# InkTime_Schematic.net
KiCad netlist of a schematic drawn in EAGLE
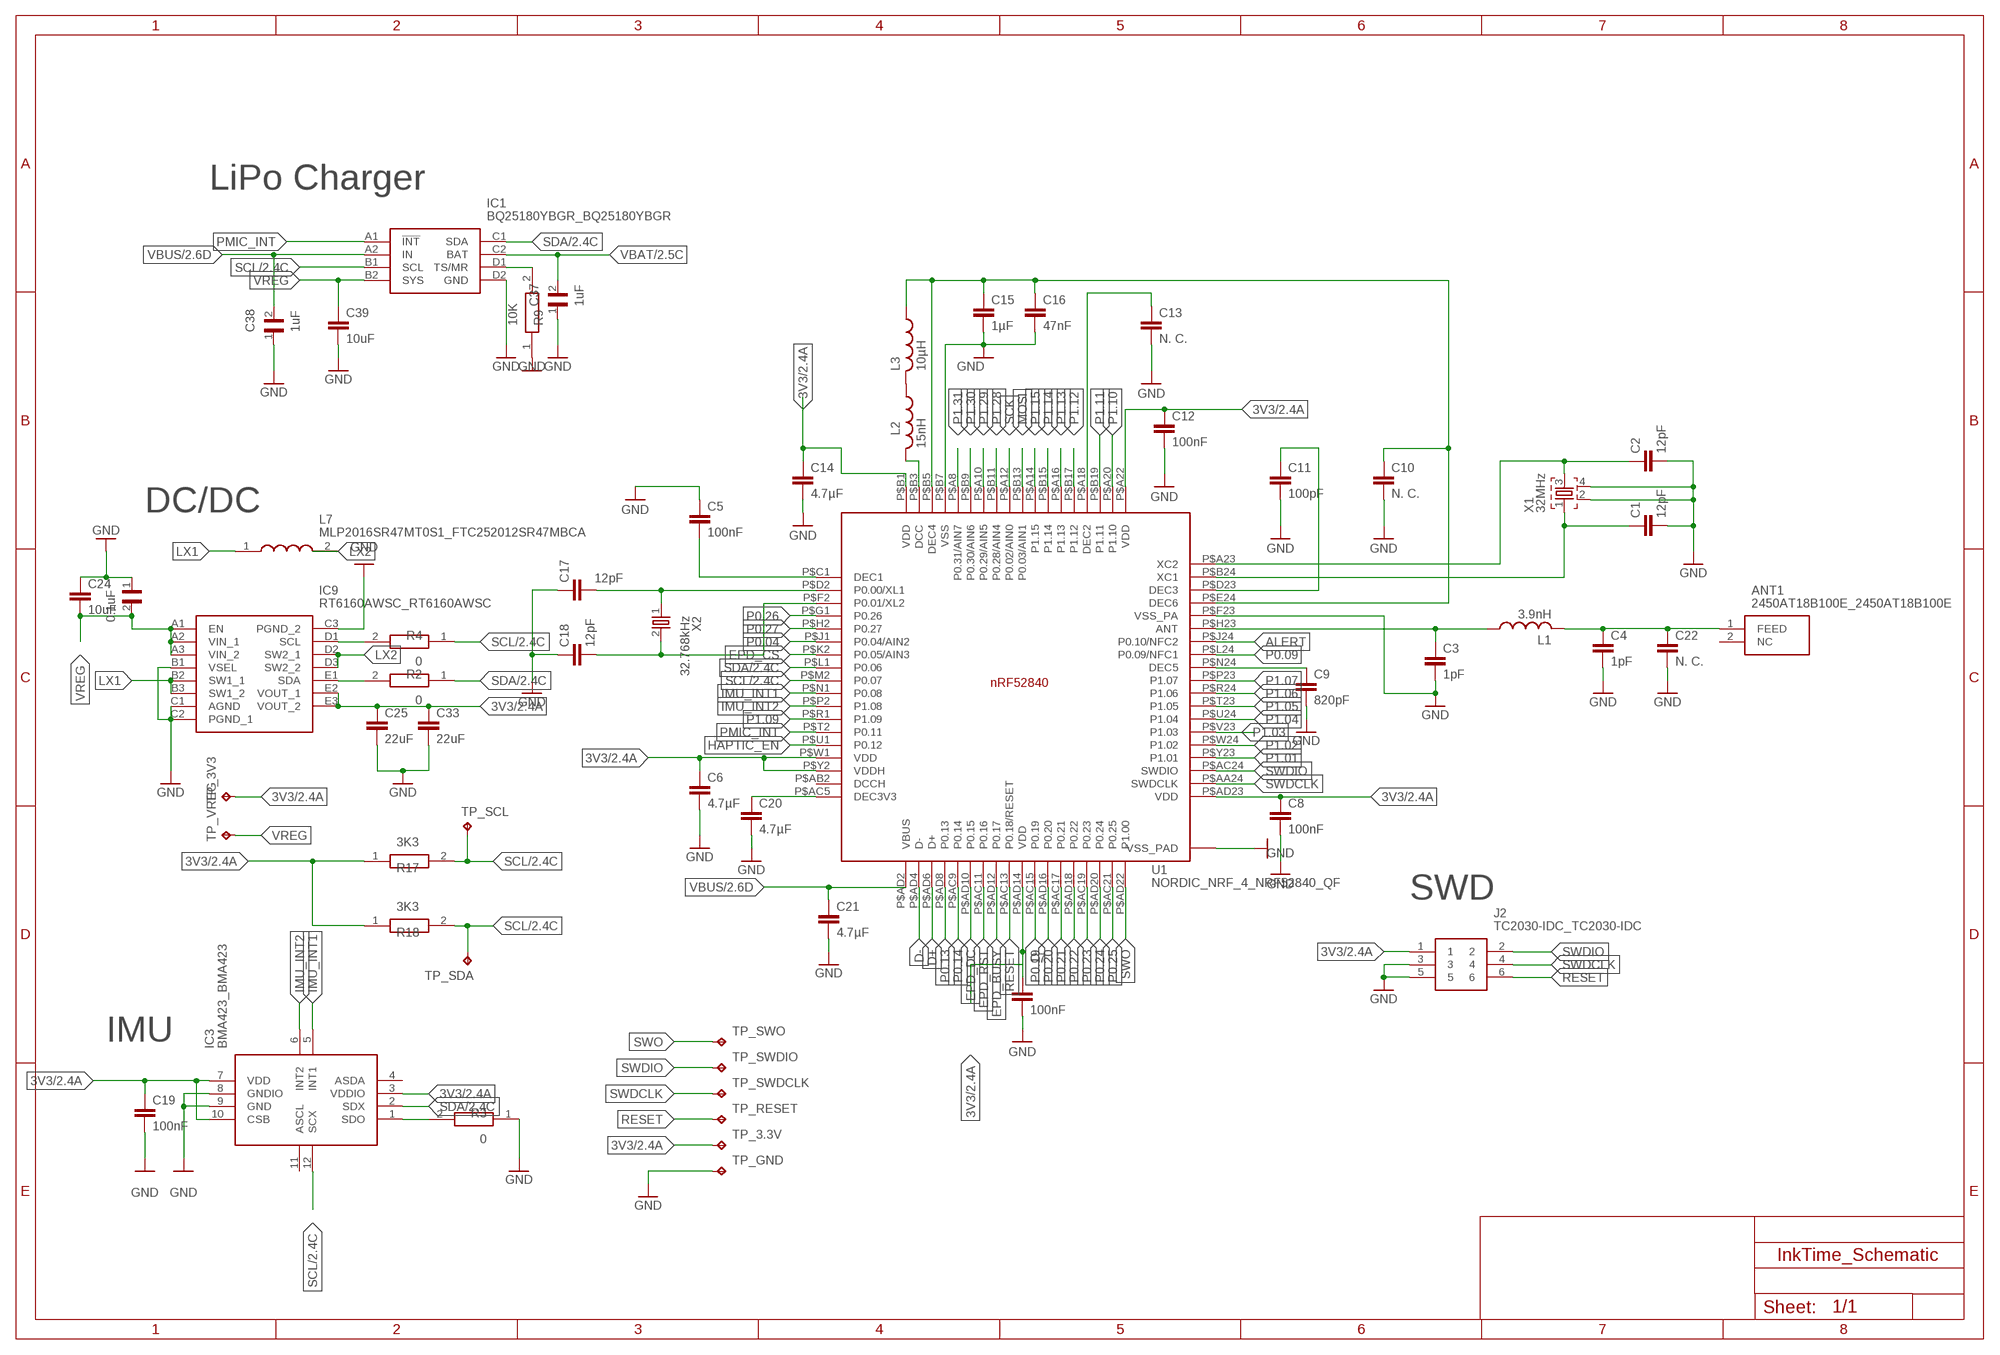
[diagram p0: schematic, sheet 1, part 1 of 2]
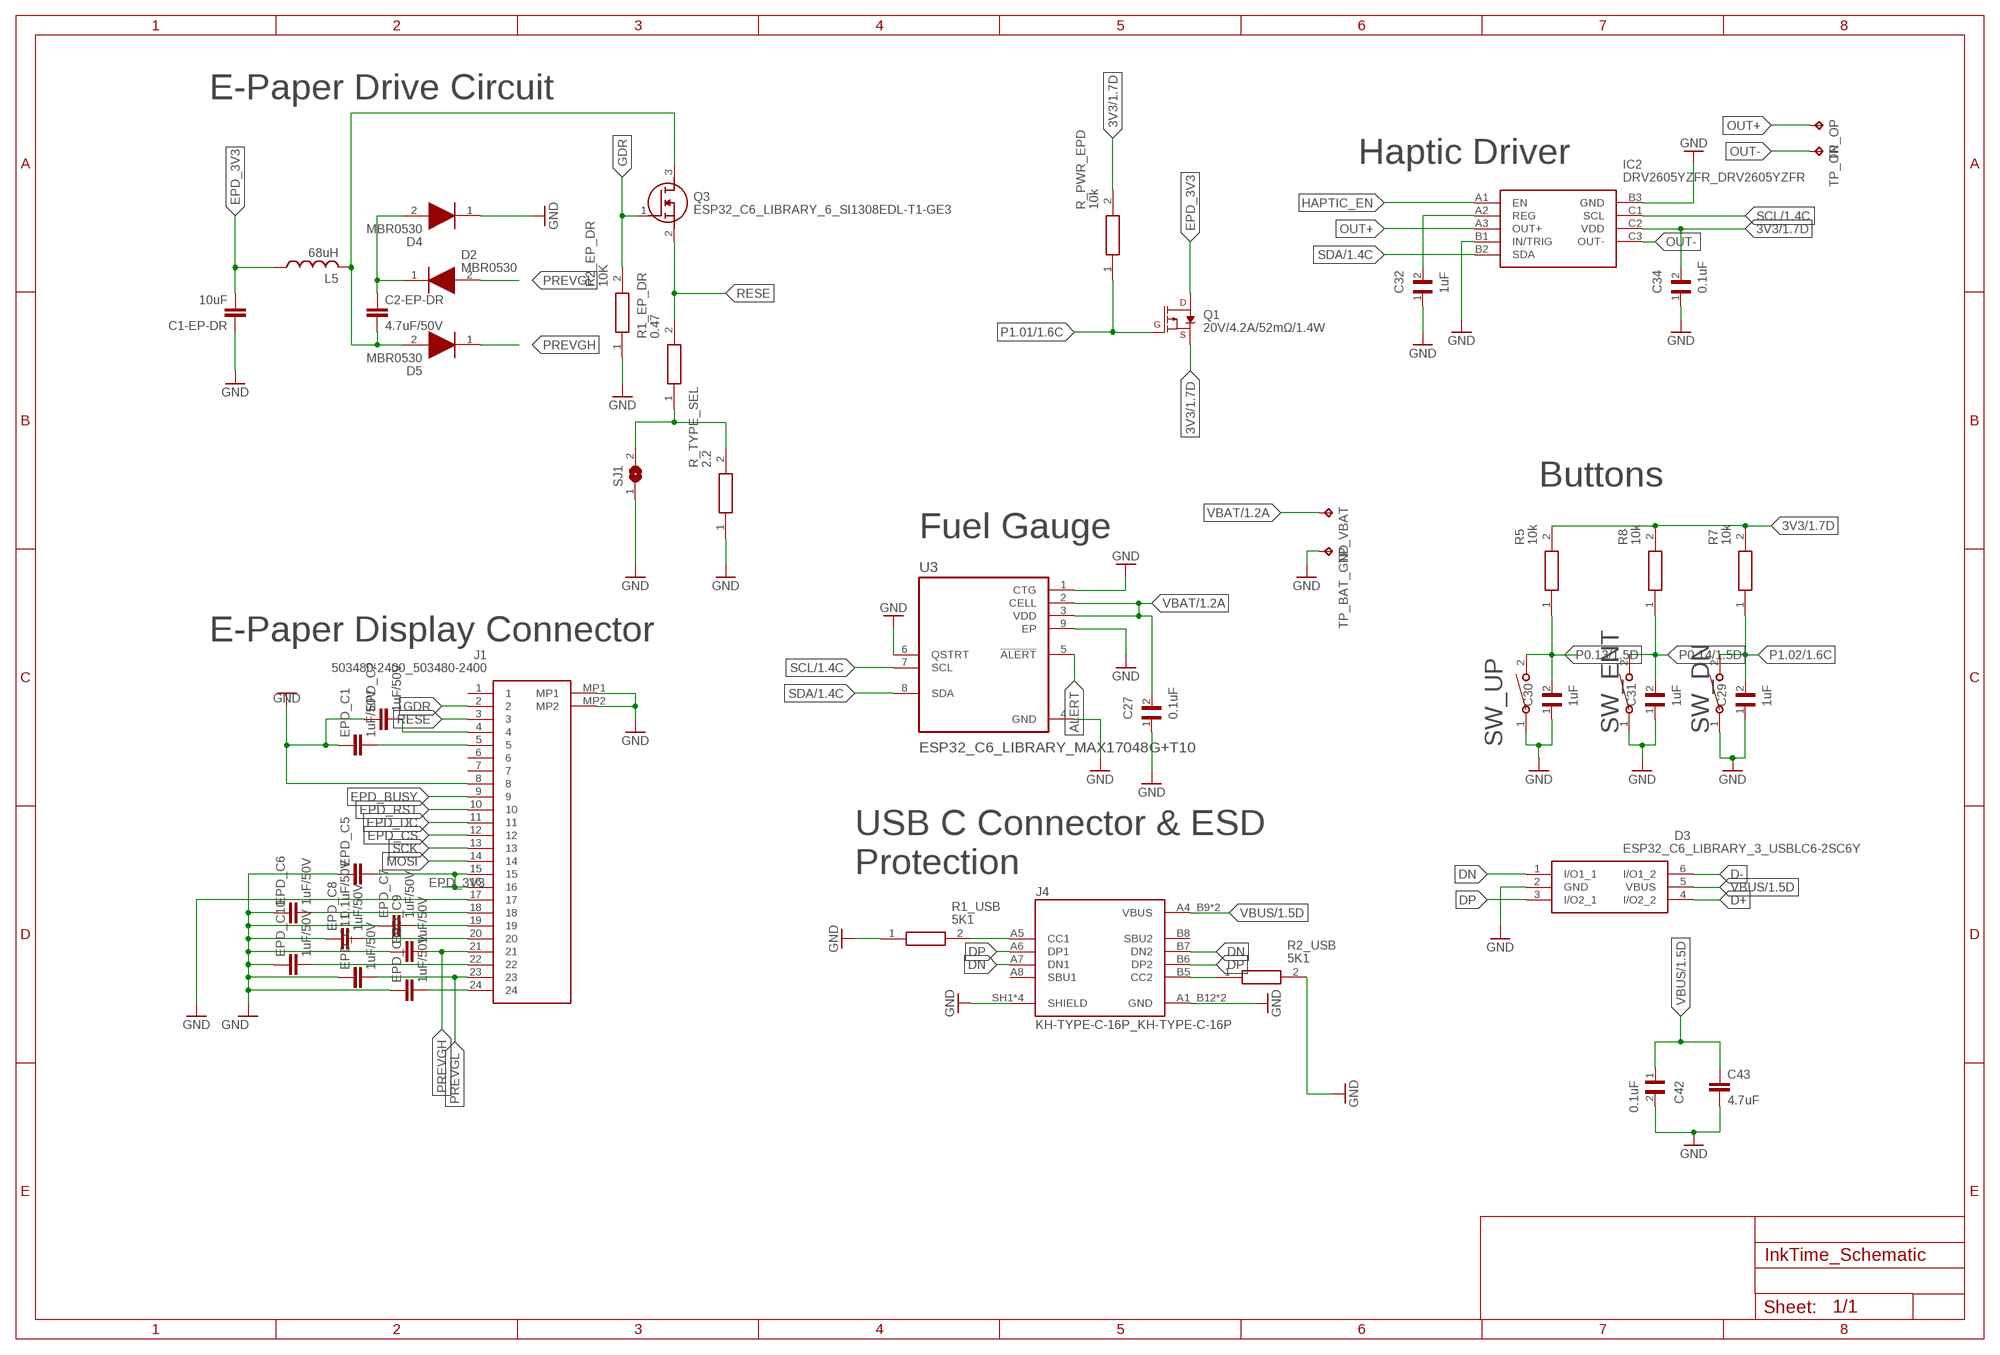
[diagram p1: schematic, sheet 1, part 2 of 2]

(export (version "E")
  (design (tool "Eeschema 10.0.6"))
  (components
    (comp (ref "ANT1")
      (value "2450AT18B100E_2450AT18B100E")
      (footprint "eagle-import:2450AT18B100E_ANTC3216X140N")
      (fields
        (field (name "ARROW_PART_NUMBER") "2450AT18B100E")
        (field (name "MOUSER_PART_NUMBER") "609-2450AT18B100E")
      )
      (libsource (lib "eagle-import") (part "2450AT18B100E_2450AT18B100E"))
    )
    (comp (ref "C1")
      (value "12pF")
      (footprint "eagle-import:NORDIC_NRF_3_RESC0201_L")
      (libsource (lib "eagle-import") (part "NORDIC_NRF_3_CAPACITOR_0201_L"))
    )
    (comp (ref "C1-EP-DR")
      (value "10uF")
      (footprint "eagle-import:NORDIC_NRF_3_RESC0402_L")
      (libsource (lib "eagle-import") (part "NORDIC_NRF_3_CAPACITOR_0402_L"))
    )
    (comp (ref "C2")
      (value "12pF")
      (footprint "eagle-import:NORDIC_NRF_3_RESC0201_L")
      (libsource (lib "eagle-import") (part "NORDIC_NRF_3_CAPACITOR_0201_L"))
    )
    (comp (ref "C2-EP-DR")
      (value "4.7uF/50V")
      (footprint "eagle-import:NORDIC_NRF_3_RESC0402_L")
      (libsource (lib "eagle-import") (part "NORDIC_NRF_3_CAPACITOR_0402_L"))
    )
    (comp (ref "C3")
      (value "1pF")
      (footprint "eagle-import:NORDIC_NRF_3_RESC0201_L")
      (libsource (lib "eagle-import") (part "NORDIC_NRF_3_CAPACITOR_0201_L"))
    )
    (comp (ref "C4")
      (value "1pF")
      (footprint "eagle-import:NORDIC_NRF_3_RESC0201_L")
      (libsource (lib "eagle-import") (part "NORDIC_NRF_3_CAPACITOR_0201_L"))
    )
    (comp (ref "C5")
      (value "100nF")
      (footprint "eagle-import:NORDIC_NRF_3_RESC0201_L")
      (libsource (lib "eagle-import") (part "NORDIC_NRF_3_CAPACITOR_0201_L"))
    )
    (comp (ref "C6")
      (value "4.7µF")
      (footprint "eagle-import:NORDIC_NRF_3_RESC0402_L")
      (libsource (lib "eagle-import") (part "NORDIC_NRF_3_CAPACITOR_0402_L"))
    )
    (comp (ref "C7")
      (value "100nF")
      (footprint "eagle-import:NORDIC_NRF_3_RESC0201_L")
      (libsource (lib "eagle-import") (part "NORDIC_NRF_3_CAPACITOR_0201_L"))
    )
    (comp (ref "C8")
      (value "100nF")
      (footprint "eagle-import:NORDIC_NRF_3_RESC0201_L")
      (libsource (lib "eagle-import") (part "NORDIC_NRF_3_CAPACITOR_0201_L"))
    )
    (comp (ref "C9")
      (value "820pF")
      (footprint "eagle-import:NORDIC_NRF_3_RESC0201_L")
      (libsource (lib "eagle-import") (part "NORDIC_NRF_3_CAPACITOR_0201_L"))
    )
    (comp (ref "C10")
      (value "N. C.")
      (footprint "eagle-import:NORDIC_NRF_3_RESC0201_L")
      (libsource (lib "eagle-import") (part "NORDIC_NRF_3_CAPACITOR_0201_L"))
    )
    (comp (ref "C11")
      (value "100pF")
      (footprint "eagle-import:NORDIC_NRF_3_RESC0201_L")
      (libsource (lib "eagle-import") (part "NORDIC_NRF_3_CAPACITOR_0201_L"))
    )
    (comp (ref "C12")
      (value "100nF")
      (footprint "eagle-import:NORDIC_NRF_3_RESC0201_L")
      (libsource (lib "eagle-import") (part "NORDIC_NRF_3_CAPACITOR_0201_L"))
    )
    (comp (ref "C13")
      (value "N. C.")
      (footprint "eagle-import:NORDIC_NRF_3_RESC0201_L")
      (libsource (lib "eagle-import") (part "NORDIC_NRF_3_CAPACITOR_0201_L"))
    )
    (comp (ref "C14")
      (value "4.7µF")
      (footprint "eagle-import:NORDIC_NRF_3_RESC0402_L")
      (libsource (lib "eagle-import") (part "NORDIC_NRF_3_CAPACITOR_0402_L"))
    )
    (comp (ref "C15")
      (value "1µF")
      (footprint "eagle-import:NORDIC_NRF_3_RESC0402_L")
      (libsource (lib "eagle-import") (part "NORDIC_NRF_3_CAPACITOR_0402_L"))
    )
    (comp (ref "C16")
      (value "47nF")
      (footprint "eagle-import:NORDIC_NRF_3_RESC0201_L")
      (libsource (lib "eagle-import") (part "NORDIC_NRF_3_CAPACITOR_0201_L"))
    )
    (comp (ref "C17")
      (value "12pF")
      (footprint "eagle-import:NORDIC_NRF_3_RESC0201_L")
      (libsource (lib "eagle-import") (part "NORDIC_NRF_3_CAPACITOR_0201_L"))
    )
    (comp (ref "C18")
      (value "12pF")
      (footprint "eagle-import:NORDIC_NRF_3_RESC0201_L")
      (libsource (lib "eagle-import") (part "NORDIC_NRF_3_CAPACITOR_0201_L"))
    )
    (comp (ref "C19")
      (value "100nF")
      (footprint "eagle-import:NORDIC_NRF_3_RESC0201_L")
      (libsource (lib "eagle-import") (part "NORDIC_NRF_3_CAPACITOR_0201_L"))
    )
    (comp (ref "C20")
      (value "4.7µF")
      (footprint "eagle-import:NORDIC_NRF_3_RESC0402_L")
      (libsource (lib "eagle-import") (part "NORDIC_NRF_3_CAPACITOR_0402_L"))
    )
    (comp (ref "C21")
      (value "4.7µF")
      (footprint "eagle-import:NORDIC_NRF_3_RESC0402_L")
      (libsource (lib "eagle-import") (part "NORDIC_NRF_3_CAPACITOR_0402_L"))
    )
    (comp (ref "C22")
      (value "N. C.")
      (footprint "eagle-import:NORDIC_NRF_3_RESC0201_L")
      (libsource (lib "eagle-import") (part "NORDIC_NRF_3_CAPACITOR_0201_L"))
    )
    (comp (ref "C23")
      (value "0.1uF")
      (footprint "eagle-import:GRM011R60J152KE01L_1_0201")
      (libsource (lib "eagle-import") (part "GRM011R60J152KE01L_1_GRM011R60J152KE01L"))
    )
    (comp (ref "C24")
      (value "10uF")
      (footprint "eagle-import:NORDIC_NRF_3_RESC0402_L")
      (libsource (lib "eagle-import") (part "NORDIC_NRF_3_CAPACITOR_0402_L"))
    )
    (comp (ref "C25")
      (value "22uF")
      (footprint "eagle-import:NORDIC_NRF_3_RESC0402_L")
      (libsource (lib "eagle-import") (part "NORDIC_NRF_3_CAPACITOR_0402_L"))
    )
    (comp (ref "C27")
      (value "0.1uF")
      (footprint "eagle-import:GRM011R60J152KE01L_1_0201")
      (libsource (lib "eagle-import") (part "GRM011R60J152KE01L_1_GRM011R60J152KE01L"))
    )
    (comp (ref "C29")
      (value "1uF")
      (footprint "eagle-import:GRM011R60J152KE01L_1_0201")
      (libsource (lib "eagle-import") (part "GRM011R60J152KE01L_1_GRM011R60J152KE01L"))
    )
    (comp (ref "C30")
      (value "1uF")
      (footprint "eagle-import:GRM011R60J152KE01L_1_0201")
      (libsource (lib "eagle-import") (part "GRM011R60J152KE01L_1_GRM011R60J152KE01L"))
    )
    (comp (ref "C31")
      (value "1uF")
      (footprint "eagle-import:GRM011R60J152KE01L_1_0201")
      (libsource (lib "eagle-import") (part "GRM011R60J152KE01L_1_GRM011R60J152KE01L"))
    )
    (comp (ref "C32")
      (value "1uF")
      (footprint "eagle-import:GRM011R60J152KE01L_1_0201")
      (libsource (lib "eagle-import") (part "GRM011R60J152KE01L_1_GRM011R60J152KE01L"))
    )
    (comp (ref "C33")
      (value "22uF")
      (footprint "eagle-import:NORDIC_NRF_3_RESC0402_L")
      (libsource (lib "eagle-import") (part "NORDIC_NRF_3_CAPACITOR_0402_L"))
    )
    (comp (ref "C34")
      (value "0.1uF")
      (footprint "eagle-import:GRM011R60J152KE01L_1_0201")
      (libsource (lib "eagle-import") (part "GRM011R60J152KE01L_1_GRM011R60J152KE01L"))
    )
    (comp (ref "C37")
      (value "1uF")
      (footprint "eagle-import:GRM011R60J152KE01L_1_0201")
      (libsource (lib "eagle-import") (part "GRM011R60J152KE01L_1_GRM011R60J152KE01L"))
    )
    (comp (ref "C38")
      (value "1uF")
      (footprint "eagle-import:GRM011R60J152KE01L_1_0201")
      (libsource (lib "eagle-import") (part "GRM011R60J152KE01L_1_GRM011R60J152KE01L"))
    )
    (comp (ref "C39")
      (value "10uF")
      (footprint "eagle-import:NORDIC_NRF_3_RESC0402_L")
      (libsource (lib "eagle-import") (part "NORDIC_NRF_3_CAPACITOR_0402_L"))
    )
    (comp (ref "C42")
      (value "0.1uF")
      (footprint "eagle-import:GRM011R60J152KE01L_1_0201")
      (libsource (lib "eagle-import") (part "GRM011R60J152KE01L_1_GRM011R60J152KE01L"))
    )
    (comp (ref "C43")
      (value "4.7uF")
      (footprint "eagle-import:NORDIC_NRF_3_RESC0402_L")
      (libsource (lib "eagle-import") (part "NORDIC_NRF_3_CAPACITOR_0402_L"))
    )
    (comp (ref "D2")
      (value "MBR0530")
      (footprint "eagle-import:ESP32_C6_LIBRARY_5_SOD3716X135N")
      (fields (field (name "MF") "ON Semiconductor"))
      (libsource (lib "eagle-import") (part "ESP32_C6_LIBRARY_5_MBR0530"))
    )
    (comp (ref "D3")
      (value "ESP32_C6_LIBRARY_3_USBLC6-2SC6Y")
      (footprint "eagle-import:ESP32_C6_LIBRARY_3_SOT95P280X145-6N")
      (fields (field (name "MF") "STMicroelectronics") (field (name "MP") "USBLC6-2SC6Y"))
      (libsource (lib "eagle-import") (part "ESP32_C6_LIBRARY_3_USBLC6-2SC6Y"))
    )
    (comp (ref "D4")
      (value "MBR0530")
      (footprint "eagle-import:ESP32_C6_LIBRARY_5_SOD3716X135N")
      (fields (field (name "MF") "ON Semiconductor"))
      (libsource (lib "eagle-import") (part "ESP32_C6_LIBRARY_5_MBR0530"))
    )
    (comp (ref "D5")
      (value "MBR0530")
      (footprint "eagle-import:ESP32_C6_LIBRARY_5_SOD3716X135N")
      (fields (field (name "MF") "ON Semiconductor"))
      (libsource (lib "eagle-import") (part "ESP32_C6_LIBRARY_5_MBR0530"))
    )
    (comp (ref "EPD_C1")
      (value "1uF/50V")
      (footprint "eagle-import:NORDIC_NRF_3_RESC0402_L")
      (libsource (lib "eagle-import") (part "NORDIC_NRF_3_CAPACITOR_0402_L"))
    )
    (comp (ref "EPD_C2")
      (value "1uF/50V")
      (footprint "eagle-import:NORDIC_NRF_3_RESC0402_L")
      (libsource (lib "eagle-import") (part "NORDIC_NRF_3_CAPACITOR_0402_L"))
    )
    (comp (ref "EPD_C5")
      (value "0.1uF/50V")
      (footprint "eagle-import:NORDIC_NRF_3_RESC0201_L")
      (libsource (lib "eagle-import") (part "NORDIC_NRF_3_CAPACITOR_0201_L"))
    )
    (comp (ref "EPD_C6")
      (value "1uF/50V")
      (footprint "eagle-import:NORDIC_NRF_3_RESC0402_L")
      (libsource (lib "eagle-import") (part "NORDIC_NRF_3_CAPACITOR_0402_L"))
    )
    (comp (ref "EPD_C7")
      (value "1uF/50V")
      (footprint "eagle-import:NORDIC_NRF_3_RESC0402_L")
      (libsource (lib "eagle-import") (part "NORDIC_NRF_3_CAPACITOR_0402_L"))
    )
    (comp (ref "EPD_C8")
      (value "1uF/50V")
      (footprint "eagle-import:NORDIC_NRF_3_RESC0402_L")
      (libsource (lib "eagle-import") (part "NORDIC_NRF_3_CAPACITOR_0402_L"))
    )
    (comp (ref "EPD_C9")
      (value "1uF/50V")
      (footprint "eagle-import:NORDIC_NRF_3_RESC0402_L")
      (libsource (lib "eagle-import") (part "NORDIC_NRF_3_CAPACITOR_0402_L"))
    )
    (comp (ref "EPD_C10")
      (value "1uF/50V")
      (footprint "eagle-import:NORDIC_NRF_3_RESC0402_L")
      (libsource (lib "eagle-import") (part "NORDIC_NRF_3_CAPACITOR_0402_L"))
    )
    (comp (ref "EPD_C11")
      (value "1uF/50V")
      (footprint "eagle-import:NORDIC_NRF_3_RESC0402_L")
      (libsource (lib "eagle-import") (part "NORDIC_NRF_3_CAPACITOR_0402_L"))
    )
    (comp (ref "EPD_C12")
      (value "1uF/50V")
      (footprint "eagle-import:NORDIC_NRF_3_RESC0402_L")
      (libsource (lib "eagle-import") (part "NORDIC_NRF_3_CAPACITOR_0402_L"))
    )
    (comp (ref "IC1")
      (value "BQ25180YBGR_BQ25180YBGR")
      (footprint "eagle-import:BQ25180YBGR_BGA8C40P2X4_100X155X50")
      (fields
        (field (name "ARROW_PART_NUMBER") "BQ25180YBGR")
        (field (name "MOUSER_PART_NUMBER") "595-BQ25180YBGR")
      )
      (libsource (lib "eagle-import") (part "BQ25180YBGR_BQ25180YBGR"))
    )
    (comp (ref "IC2")
      (value "DRV2605YZFR_DRV2605YZFR")
      (footprint "eagle-import:DRV2605YZFR_BGA9C50P3X3_144X144X62")
      (fields (field (name "ARROW_PART_NUMBER") "DRV2605YZFR"))
      (libsource (lib "eagle-import") (part "DRV2605YZFR_DRV2605YZFR"))
    )
    (comp (ref "IC3")
      (value "BMA423_BMA423")
      (footprint "eagle-import:BMA423_BMA423")
      (fields (field (name "ARROW_PART_NUMBER") "BMA423") (field (name "MOUSER_PART_NUMBER") "262-BMA423"))
      (libsource (lib "eagle-import") (part "BMA423_BMA423"))
    )
    (comp (ref "IC9")
      (value "RT6160AWSC_RT6160AWSC")
      (footprint "eagle-import:RT6160AWSC_BGA15C40P3X5_140X230X60")
      (fields
        (field (name "MANUFACTURER_PART_NUMBER") "RT6160AWSC")
        (field (name "MOUSER_PART_NUMBER") "835-RT6160AWSC")
      )
      (libsource (lib "eagle-import") (part "RT6160AWSC_RT6160AWSC"))
    )
    (comp (ref "J1")
      (value "503480-2400_503480-2400")
      (footprint "eagle-import:503480-2400_5034802400")
      (fields
        (field (name "MANUFACTURER_PART_NUMBER") "503480-2400")
        (field (name "MOUSER_PART_NUMBER") "538-503480-2400")
      )
      (libsource (lib "eagle-import") (part "503480-2400_503480-2400"))
    )
    (comp (ref "J2")
      (value "TC2030-IDC_TC2030-IDC")
      (footprint "eagle-import:TC2030-IDC_TC2030IDC")
      (fields (field (name "MANUFACTURER_PART_NUMBER") "TC2030-IDC"))
      (libsource (lib "eagle-import") (part "TC2030-IDC_TC2030-IDC"))
    )
    (comp (ref "J4")
      (value "KH-TYPE-C-16P_KH-TYPE-C-16P")
      (footprint "eagle-import:KH-TYPE-C-16P_KINGHELM_KH-TYPE-C-16P")
      (fields (field (name "MF") "kinghelm") (field (name "MP") "KH-TYPE-C-16P"))
      (libsource (lib "eagle-import") (part "KH-TYPE-C-16P_KH-TYPE-C-16P"))
    )
    (comp (ref "L1")
      (value "3.9nH")
      (footprint "eagle-import:NORDIC_NRF_2_RESC0201_L")
      (libsource (lib "eagle-import") (part "NORDIC_NRF_2_INDUCTOR_0201_L"))
    )
    (comp (ref "L2")
      (value "15nH")
      (footprint "eagle-import:NORDIC_NRF_2_RESC0201_L")
      (libsource (lib "eagle-import") (part "NORDIC_NRF_2_INDUCTOR_0201_L"))
    )
    (comp (ref "L3")
      (value "10µH")
      (footprint "eagle-import:NORDIC_NRF_2_RESC0603_L")
      (libsource (lib "eagle-import") (part "NORDIC_NRF_2_INDUCTOR_0603_L"))
    )
    (comp (ref "L5")
      (value "68uH")
      (footprint "eagle-import:NORDIC_NRF_2_RESC0805_L")
      (libsource (lib "eagle-import") (part "NORDIC_NRF_2_INDUCTOR_0805_L"))
    )
    (comp (ref "L7")
      (value "MLP2016SR47MT0S1_FTC252012SR47MBCA")
      (footprint "eagle-import:MLP2016SR47MT0S1_INDC2016X100N")
      (fields (field (name "MANUFACTURER_PART_NUMBER") "FTC252012SR47MBCA"))
      (libsource (lib "eagle-import") (part "MLP2016SR47MT0S1_FTC252012SR47MBCA"))
    )
    (comp (ref "Q1")
      (value "20V/4.2A/52mΩ/1.4W")
      (footprint "eagle-import:ESP32_C6_LIBRARY_4_ESP32_C6_LIBRARY_4_ESP32_C6_LIBRARY_4_ESP32_C6_LIBRARY_4_ESP32_WROVER_SPARKFUN-DISCRETESEMI_SOT23-3")
      (libsource (lib "eagle-import") (part "ESP32_C6_LIBRARY_4_ESP32_WROVER_SPARKFUN-DISCRETESEMI_MOSFET_PCH-DMG2305UX-7"))
    )
    (comp (ref "Q3")
      (value "ESP32_C6_LIBRARY_6_SI1308EDL-T1-GE3")
      (footprint "eagle-import:ESP32_C6_LIBRARY_6_SOT65P210X110-3N")
      (fields (field (name "MF") "Vishay Siliconix") (field (name "MP") "SI1308EDL-T1-GE3"))
      (libsource (lib "eagle-import") (part "ESP32_C6_LIBRARY_6_SI1308EDL-T1-GE3"))
    )
    (comp (ref "R1_EP_DR")
      (value "0.47")
      (footprint "eagle-import:ERA-1AEB3401C_0201")
      (libsource (lib "eagle-import") (part "ERA-1AEB3401C_CPF0201D7K68C1"))
    )
    (comp (ref "R1_USB")
      (value "5K1")
      (footprint "eagle-import:ERA-1AEB3401C_0201")
      (libsource (lib "eagle-import") (part "ERA-1AEB3401C_CPF0201D7K68C1"))
    )
    (comp (ref "R2")
      (value "0")
      (footprint "eagle-import:CPF0201D7K68C1_0201")
      (libsource (lib "eagle-import") (part "CPF0201D7K68C1_CPF0201D7K68C1"))
    )
    (comp (ref "R2_EP_DR")
      (value "10K")
      (footprint "eagle-import:ERA-1AEB3401C_0201")
      (libsource (lib "eagle-import") (part "ERA-1AEB3401C_CPF0201D7K68C1"))
    )
    (comp (ref "R2_USB")
      (value "5K1")
      (footprint "eagle-import:ERA-1AEB3401C_0201")
      (libsource (lib "eagle-import") (part "ERA-1AEB3401C_CPF0201D7K68C1"))
    )
    (comp (ref "R3")
      (value "0")
      (footprint "eagle-import:CPF0201D7K68C1_0201")
      (libsource (lib "eagle-import") (part "CPF0201D7K68C1_CPF0201D7K68C1"))
    )
    (comp (ref "R4")
      (value "0")
      (footprint "eagle-import:CPF0201D7K68C1_0201")
      (libsource (lib "eagle-import") (part "CPF0201D7K68C1_CPF0201D7K68C1"))
    )
    (comp (ref "R5")
      (value "10k")
      (footprint "eagle-import:ERA-1AEB3401C_0201")
      (libsource (lib "eagle-import") (part "ERA-1AEB3401C_CPF0201D7K68C1"))
    )
    (comp (ref "R7")
      (value "10k")
      (footprint "eagle-import:ERA-1AEB3401C_0201")
      (libsource (lib "eagle-import") (part "ERA-1AEB3401C_CPF0201D7K68C1"))
    )
    (comp (ref "R8")
      (value "10k")
      (footprint "eagle-import:ERA-1AEB3401C_0201")
      (libsource (lib "eagle-import") (part "ERA-1AEB3401C_CPF0201D7K68C1"))
    )
    (comp (ref "R9")
      (value "10K")
      (footprint "eagle-import:CPF0201D7K68C1_0201")
      (libsource (lib "eagle-import") (part "CPF0201D7K68C1_CPF0201D7K68C1"))
    )
    (comp (ref "R17")
      (value "3K3")
      (footprint "eagle-import:CPF0201D7K68C1_0201")
      (libsource (lib "eagle-import") (part "CPF0201D7K68C1_CPF0201D7K68C1"))
    )
    (comp (ref "R18")
      (value "3K3")
      (footprint "eagle-import:CPF0201D7K68C1_0201")
      (libsource (lib "eagle-import") (part "CPF0201D7K68C1_CPF0201D7K68C1"))
    )
    (comp (ref "R_PWR_EPD")
      (value "10k")
      (footprint "eagle-import:ERA-1AEB3401C_0201")
      (libsource (lib "eagle-import") (part "ERA-1AEB3401C_CPF0201D7K68C1"))
    )
    (comp (ref "R_TYPE_SEL")
      (value "2.2")
      (footprint "eagle-import:ERA-1AEB3401C_0201")
      (libsource (lib "eagle-import") (part "ERA-1AEB3401C_CPF0201D7K68C1"))
    )
    (comp (ref "SJ1")
      (value "ESP32_C6_LIBRARY_7_JUMPER_SJ")
      (footprint "eagle-import:ESP32_C6_LIBRARY_7_JUMPER_SJ")
      (libsource (lib "eagle-import") (part "ESP32_C6_LIBRARY_7_JUMPER_SJ"))
    )
    (comp (ref "SW_DN")
      (value "2025-10-22_07-23-44_LIBRARY_EVP-AKE31ASW_EVP-AKE31A_PAN")
      (footprint "eagle-import:2025-10-22_07-23-44_LIBRARY_SW_EVP-AKE31A_PAN")
      (fields
        (field (name "MANUFACTURER_PART_NUMBER") "EVP-AKE31A")
        (field (name "COPYRIGHT") "Copyright (C) 2025 Ultra Librarian. All rights reserved.")
      )
      (libsource (lib "eagle-import") (part "2025-10-22_07-23-44_LIBRARY_EVP-AKE31ASW_EVP-AKE31A_PAN"))
    )
    (comp (ref "SW_ENT")
      (value "2025-10-22_07-23-44_LIBRARY_EVP-AKE31ASW_EVP-AKE31A_PAN")
      (footprint "eagle-import:2025-10-22_07-23-44_LIBRARY_SW_EVP-AKE31A_PAN")
      (fields
        (field (name "MANUFACTURER_PART_NUMBER") "EVP-AKE31A")
        (field (name "COPYRIGHT") "Copyright (C) 2025 Ultra Librarian. All rights reserved.")
      )
      (libsource (lib "eagle-import") (part "2025-10-22_07-23-44_LIBRARY_EVP-AKE31ASW_EVP-AKE31A_PAN"))
    )
    (comp (ref "SW_UP")
      (value "2025-10-22_07-23-44_LIBRARY_EVP-AKE31ASW_EVP-AKE31A_PAN")
      (footprint "eagle-import:2025-10-22_07-23-44_LIBRARY_SW_EVP-AKE31A_PAN")
      (fields
        (field (name "MANUFACTURER_PART_NUMBER") "EVP-AKE31A")
        (field (name "COPYRIGHT") "Copyright (C) 2025 Ultra Librarian. All rights reserved.")
      )
      (libsource (lib "eagle-import") (part "2025-10-22_07-23-44_LIBRARY_EVP-AKE31ASW_EVP-AKE31A_PAN"))
    )
    (comp (ref "TP_3.3V")
      (value "HECTOR_WATCH_1_TPTP20R")
      (footprint "eagle-import:HECTOR_WATCH_1_TP20R")
      (libsource (lib "eagle-import") (part "HECTOR_WATCH_1_TPTP20R"))
    )
    (comp (ref "TP_3V3")
      (value "HECTOR_WATCH_1_TPTP20R")
      (footprint "eagle-import:HECTOR_WATCH_1_TP20R")
      (libsource (lib "eagle-import") (part "HECTOR_WATCH_1_TPTP20R"))
    )
    (comp (ref "TP_BAT_GND")
      (value "HECTOR_WATCH_1_TPTP20R")
      (footprint "eagle-import:HECTOR_WATCH_1_TP20R")
      (libsource (lib "eagle-import") (part "HECTOR_WATCH_1_TPTP20R"))
    )
    (comp (ref "TP_GND")
      (value "HECTOR_WATCH_1_TPTP20R")
      (footprint "eagle-import:HECTOR_WATCH_1_TP20R")
      (libsource (lib "eagle-import") (part "HECTOR_WATCH_1_TPTP20R"))
    )
    (comp (ref "TP_ON")
      (value "HECTOR_WATCH_1_TPTP20R")
      (footprint "eagle-import:HECTOR_WATCH_1_TP20R")
      (libsource (lib "eagle-import") (part "HECTOR_WATCH_1_TPTP20R"))
    )
    (comp (ref "TP_OP")
      (value "HECTOR_WATCH_1_TPTP20R")
      (footprint "eagle-import:HECTOR_WATCH_1_TP20R")
      (libsource (lib "eagle-import") (part "HECTOR_WATCH_1_TPTP20R"))
    )
    (comp (ref "TP_RESET")
      (value "HECTOR_WATCH_1_TPTP20R")
      (footprint "eagle-import:HECTOR_WATCH_1_TP20R")
      (libsource (lib "eagle-import") (part "HECTOR_WATCH_1_TPTP20R"))
    )
    (comp (ref "TP_SCL")
      (value "HECTOR_WATCH_1_TPTP20R")
      (footprint "eagle-import:HECTOR_WATCH_1_TP20R")
      (libsource (lib "eagle-import") (part "HECTOR_WATCH_1_TPTP20R"))
    )
    (comp (ref "TP_SDA")
      (value "HECTOR_WATCH_1_TPTP20R")
      (footprint "eagle-import:HECTOR_WATCH_1_TP20R")
      (libsource (lib "eagle-import") (part "HECTOR_WATCH_1_TPTP20R"))
    )
    (comp (ref "TP_SWDCLK")
      (value "HECTOR_WATCH_1_TPTP20R")
      (footprint "eagle-import:HECTOR_WATCH_1_TP20R")
      (libsource (lib "eagle-import") (part "HECTOR_WATCH_1_TPTP20R"))
    )
    (comp (ref "TP_SWDIO")
      (value "HECTOR_WATCH_1_TPTP20R")
      (footprint "eagle-import:HECTOR_WATCH_1_TP20R")
      (libsource (lib "eagle-import") (part "HECTOR_WATCH_1_TPTP20R"))
    )
    (comp (ref "TP_SWO")
      (value "HECTOR_WATCH_1_TPTP20R")
      (footprint "eagle-import:HECTOR_WATCH_1_TP20R")
      (libsource (lib "eagle-import") (part "HECTOR_WATCH_1_TPTP20R"))
    )
    (comp (ref "TP_VBAT")
      (value "HECTOR_WATCH_1_TPTP20R")
      (footprint "eagle-import:HECTOR_WATCH_1_TP20R")
      (libsource (lib "eagle-import") (part "HECTOR_WATCH_1_TPTP20R"))
    )
    (comp (ref "TP_VREG")
      (value "HECTOR_WATCH_1_TPTP20R")
      (footprint "eagle-import:HECTOR_WATCH_1_TP20R")
      (libsource (lib "eagle-import") (part "HECTOR_WATCH_1_TPTP20R"))
    )
    (comp (ref "U1")
      (value "NORDIC_NRF_4_NRF52840_QF")
      (footprint "eagle-import:NORDIC_NRF_4_AQFN50P700X700X85_HS-74N")
      (libsource (lib "eagle-import") (part "NORDIC_NRF_4_NRF52840_QF"))
    )
    (comp (ref "U3")
      (value "ESP32_C6_LIBRARY_MAX17048G+T10")
      (footprint "eagle-import:ESP32_C6_LIBRARY_SON50P200X200X80-9N")
      (fields (field (name "MF") "Analog Devices") (field (name "MP") "MAX17048G+T10"))
      (libsource (lib "eagle-import") (part "ESP32_C6_LIBRARY_MAX17048G+T10"))
    )
    (comp (ref "X1")
      (value "32MHz")
      (footprint "eagle-import:NORDIC_NRF_BT-XTAL_2016_N")
      (libsource (lib "eagle-import") (part "NORDIC_NRF_XTAL_32MHZ"))
    )
    (comp (ref "X2")
      (value "32.768kHz")
      (footprint "eagle-import:NORDIC_NRF_1_XTAL_3215_N")
      (libsource (lib "eagle-import") (part "NORDIC_NRF_1_XTAL_32KHZ"))
    )
  )
  (nets
    (net (code "1") (name "3V3{slash}1.7D") (class "Default")
      (node (ref "C34") (pin "2") (pinfunction "2_2") (pintype "passive"))
      (node (ref "IC2") (pin "C2") (pinfunction "VDD_C2") (pintype "bidirectional"))
      (node (ref "Q1") (pin "2") (pinfunction "S_2") (pintype "bidirectional"))
      (node (ref "R5") (pin "2") (pinfunction "2_2") (pintype "bidirectional"))
      (node (ref "R7") (pin "2") (pinfunction "2_2") (pintype "bidirectional"))
      (node (ref "R8") (pin "2") (pinfunction "2_2") (pintype "bidirectional"))
      (node (ref "R_PWR_EPD") (pin "2") (pinfunction "2_2") (pintype "bidirectional"))
    )
    (net (code "2") (name "3V3{slash}2.4A") (class "Default")
      (node (ref "C12") (pin "1") (pinfunction "1_1") (pintype "passive"))
      (node (ref "C14") (pin "1") (pinfunction "1_1") (pintype "passive"))
      (node (ref "C19") (pin "1") (pinfunction "1_1") (pintype "passive"))
      (node (ref "C25") (pin "1") (pinfunction "1_1") (pintype "passive"))
      (node (ref "C33") (pin "1") (pinfunction "1_1") (pintype "passive"))
      (node (ref "C6") (pin "1") (pinfunction "1_1") (pintype "passive"))
      (node (ref "C7") (pin "1") (pinfunction "1_1") (pintype "passive"))
      (node (ref "C8") (pin "1") (pinfunction "1_1") (pintype "passive"))
      (node (ref "IC3") (pin "10") (pinfunction "CSB_10") (pintype "bidirectional"))
      (node (ref "IC3") (pin "3") (pinfunction "VDDIO_3") (pintype "bidirectional"))
      (node (ref "IC3") (pin "7") (pinfunction "VDD_7") (pintype "bidirectional"))
      (node (ref "IC9") (pin "E2") (pinfunction "VOUT_1_E2") (pintype "bidirectional"))
      (node (ref "IC9") (pin "E3") (pinfunction "VOUT_2_E3") (pintype "bidirectional"))
      (node (ref "J2") (pin "1") (pinfunction "1_1") (pintype "bidirectional"))
      (node (ref "R17") (pin "1") (pinfunction "1_1") (pintype "bidirectional"))
      (node (ref "R18") (pin "1") (pinfunction "1_1") (pintype "bidirectional"))
      (node (ref "TP_3.3V") (pin "TP") (pinfunction "TP_TP") (pintype "input"))
      (node (ref "TP_3V3") (pin "TP") (pinfunction "TP_TP") (pintype "input"))
      (node (ref "U1") (pin "P$A22") (pinfunction "VDD_P$A22") (pintype "power_in"))
      (node (ref "U1") (pin "P$AD14") (pinfunction "VDD_P$AD14") (pintype "power_in"))
      (node (ref "U1") (pin "P$AD23") (pinfunction "VDD_P$AD23") (pintype "power_in"))
      (node (ref "U1") (pin "P$B1") (pinfunction "VDD_P$B1") (pintype "power_in"))
      (node (ref "U1") (pin "P$W1") (pinfunction "VDD_P$W1") (pintype "power_in"))
      (node (ref "U1") (pin "P$Y2") (pinfunction "VDDH_P$Y2") (pintype "power_in"))
    )
    (net (code "3") (name "ALERT") (class "Default")
      (node (ref "U1") (pin "P$J24") (pinfunction "P0.10/NFC2_P$J24") (pintype "bidirectional"))
      (node (ref "U3") (pin "5") (pinfunction "~{ALERT}_5") (pintype "output"))
    )
    (net (code "4") (name "D+") (class "Default")
      (node (ref "D3") (pin "4") (pinfunction "I/O2_2_4") (pintype "bidirectional"))
      (node (ref "U1") (pin "P$AD6") (pinfunction "D+_P$AD6") (pintype "bidirectional"))
    )
    (net (code "5") (name "D-") (class "Default")
      (node (ref "D3") (pin "6") (pinfunction "I/O1_2_6") (pintype "bidirectional"))
      (node (ref "U1") (pin "P$AD4") (pinfunction "D-_P$AD4") (pintype "bidirectional"))
    )
    (net (code "6") (name "DN") (class "Default")
      (node (ref "D3") (pin "1") (pinfunction "I/O1_1_1") (pintype "bidirectional"))
      (node (ref "J4") (pin "A7") (pinfunction "DN1_A7") (pintype "bidirectional"))
      (node (ref "J4") (pin "B7") (pinfunction "DN2_B7") (pintype "bidirectional"))
    )
    (net (code "7") (name "DP") (class "Default")
      (node (ref "D3") (pin "3") (pinfunction "I/O2_1_3") (pintype "bidirectional"))
      (node (ref "J4") (pin "A6") (pinfunction "DP1_A6") (pintype "bidirectional"))
      (node (ref "J4") (pin "B6") (pinfunction "DP2_B6") (pintype "bidirectional"))
    )
    (net (code "8") (name "EPD_3V3") (class "Default")
      (node (ref "C1-EP-DR") (pin "2") (pinfunction "2_2") (pintype "passive"))
      (node (ref "EPD_C5") (pin "2") (pinfunction "2_2") (pintype "passive"))
      (node (ref "J1") (pin "15") (pinfunction "15_15") (pintype "bidirectional"))
      (node (ref "J1") (pin "16") (pinfunction "16_16") (pintype "bidirectional"))
      (node (ref "L5") (pin "1") (pinfunction "1_1") (pintype "passive"))
      (node (ref "Q1") (pin "3") (pinfunction "D_3") (pintype "bidirectional"))
    )
    (net (code "9") (name "EPD_BUSY") (class "Default")
      (node (ref "J1") (pin "9") (pinfunction "9_9") (pintype "bidirectional"))
      (node (ref "U1") (pin "P$AD12") (pinfunction "P0.17_P$AD12") (pintype "bidirectional"))
    )
    (net (code "10") (name "EPD_CS") (class "Default")
      (node (ref "J1") (pin "12") (pinfunction "12_12") (pintype "bidirectional"))
      (node (ref "U1") (pin "P$K2") (pinfunction "P0.05/AIN3_P$K2") (pintype "bidirectional"))
    )
    (net (code "11") (name "EPD_DC") (class "Default")
      (node (ref "J1") (pin "11") (pinfunction "11_11") (pintype "bidirectional"))
      (node (ref "U1") (pin "P$AD10") (pinfunction "P0.15_P$AD10") (pintype "bidirectional"))
    )
    (net (code "12") (name "EPD_RST") (class "Default")
      (node (ref "J1") (pin "10") (pinfunction "10_10") (pintype "bidirectional"))
      (node (ref "U1") (pin "P$AC11") (pinfunction "P0.16_P$AC11") (pintype "bidirectional"))
    )
    (net (code "13") (name "GDR") (class "Default")
      (node (ref "J1") (pin "2") (pinfunction "2_2") (pintype "bidirectional"))
      (node (ref "Q3") (pin "1") (pinfunction "G_1") (pintype "bidirectional"))
      (node (ref "R2_EP_DR") (pin "2") (pinfunction "2_2") (pintype "bidirectional"))
    )
    (net (code "14") (name "GND") (class "Default")
      (node (ref "C1") (pin "2") (pinfunction "2_2") (pintype "passive"))
      (node (ref "C1-EP-DR") (pin "1") (pinfunction "1_1") (pintype "passive"))
      (node (ref "C10") (pin "2") (pinfunction "2_2") (pintype "passive"))
      (node (ref "C11") (pin "2") (pinfunction "2_2") (pintype "passive"))
      (node (ref "C12") (pin "2") (pinfunction "2_2") (pintype "passive"))
      (node (ref "C13") (pin "2") (pinfunction "2_2") (pintype "passive"))
      (node (ref "C14") (pin "2") (pinfunction "2_2") (pintype "passive"))
      (node (ref "C15") (pin "2") (pinfunction "2_2") (pintype "passive"))
      (node (ref "C16") (pin "2") (pinfunction "2_2") (pintype "passive"))
      (node (ref "C17") (pin "1") (pinfunction "1_1") (pintype "passive"))
      (node (ref "C18") (pin "1") (pinfunction "1_1") (pintype "passive"))
      (node (ref "C19") (pin "2") (pinfunction "2_2") (pintype "passive"))
      (node (ref "C2") (pin "2") (pinfunction "2_2") (pintype "passive"))
      (node (ref "C20") (pin "2") (pinfunction "2_2") (pintype "passive"))
      (node (ref "C21") (pin "2") (pinfunction "2_2") (pintype "passive"))
      (node (ref "C22") (pin "2") (pinfunction "2_2") (pintype "passive"))
      (node (ref "C23") (pin "1") (pinfunction "1_1") (pintype "passive"))
      (node (ref "C24") (pin "1") (pinfunction "1_1") (pintype "passive"))
      (node (ref "C25") (pin "2") (pinfunction "2_2") (pintype "passive"))
      (node (ref "C27") (pin "1") (pinfunction "1_1") (pintype "passive"))
      (node (ref "C29") (pin "1") (pinfunction "1_1") (pintype "passive"))
      (node (ref "C3") (pin "2") (pinfunction "2_2") (pintype "passive"))
      (node (ref "C30") (pin "1") (pinfunction "1_1") (pintype "passive"))
      (node (ref "C31") (pin "1") (pinfunction "1_1") (pintype "passive"))
      (node (ref "C32") (pin "1") (pinfunction "1_1") (pintype "passive"))
      (node (ref "C33") (pin "2") (pinfunction "2_2") (pintype "passive"))
      (node (ref "C34") (pin "1") (pinfunction "1_1") (pintype "passive"))
      (node (ref "C37") (pin "1") (pinfunction "1_1") (pintype "passive"))
      (node (ref "C38") (pin "1") (pinfunction "1_1") (pintype "passive"))
      (node (ref "C39") (pin "2") (pinfunction "2_2") (pintype "passive"))
      (node (ref "C4") (pin "2") (pinfunction "2_2") (pintype "passive"))
      (node (ref "C42") (pin "2") (pinfunction "2_2") (pintype "passive"))
      (node (ref "C43") (pin "2") (pinfunction "2_2") (pintype "passive"))
      (node (ref "C5") (pin "1") (pinfunction "1_1") (pintype "passive"))
      (node (ref "C6") (pin "2") (pinfunction "2_2") (pintype "passive"))
      (node (ref "C7") (pin "2") (pinfunction "2_2") (pintype "passive"))
      (node (ref "C8") (pin "2") (pinfunction "2_2") (pintype "passive"))
      (node (ref "C9") (pin "2") (pinfunction "2_2") (pintype "passive"))
      (node (ref "D3") (pin "2") (pinfunction "GND_2") (pintype "bidirectional"))
      (node (ref "D4") (pin "1") (pinfunction "K_1") (pintype "bidirectional"))
      (node (ref "EPD_C1") (pin "1") (pinfunction "1_1") (pintype "passive"))
      (node (ref "EPD_C10") (pin "1") (pinfunction "1_1") (pintype "passive"))
      (node (ref "EPD_C11") (pin "1") (pinfunction "1_1") (pintype "passive"))
      (node (ref "EPD_C12") (pin "1") (pinfunction "1_1") (pintype "passive"))
      (node (ref "EPD_C2") (pin "1") (pinfunction "1_1") (pintype "passive"))
      (node (ref "EPD_C5") (pin "1") (pinfunction "1_1") (pintype "passive"))
      (node (ref "EPD_C6") (pin "1") (pinfunction "1_1") (pintype "passive"))
      (node (ref "EPD_C7") (pin "1") (pinfunction "1_1") (pintype "passive"))
      (node (ref "EPD_C8") (pin "1") (pinfunction "1_1") (pintype "passive"))
      (node (ref "EPD_C9") (pin "1") (pinfunction "1_1") (pintype "passive"))
      (node (ref "IC1") (pin "D2") (pinfunction "GND_D2") (pintype "bidirectional"))
      (node (ref "IC2") (pin "B1") (pinfunction "IN/TRIG_B1") (pintype "bidirectional"))
      (node (ref "IC2") (pin "B3") (pinfunction "GND_B3") (pintype "bidirectional"))
      (node (ref "IC3") (pin "8") (pinfunction "GNDIO_8") (pintype "bidirectional"))
      (node (ref "IC3") (pin "9") (pinfunction "GND_9") (pintype "bidirectional"))
      (node (ref "IC9") (pin "B1") (pinfunction "VSEL_B1") (pintype "bidirectional"))
      (node (ref "IC9") (pin "C1") (pinfunction "AGND_C1") (pintype "bidirectional"))
      (node (ref "IC9") (pin "C2") (pinfunction "PGND_1_C2") (pintype "bidirectional"))
      (node (ref "IC9") (pin "C3") (pinfunction "PGND_2_C3") (pintype "bidirectional"))
      (node (ref "J1") (pin "17") (pinfunction "17_17") (pintype "bidirectional"))
      (node (ref "J1") (pin "8") (pinfunction "8_8") (pintype "bidirectional"))
      (node (ref "J1") (pin "MP1") (pinfunction "MP1_MP1") (pintype "bidirectional"))
      (node (ref "J1") (pin "MP2") (pinfunction "MP2_MP2") (pintype "bidirectional"))
      (node (ref "J2") (pin "3") (pinfunction "3_3") (pintype "bidirectional"))
      (node (ref "J2") (pin "5") (pinfunction "5_5") (pintype "bidirectional"))
      (node (ref "J4") (pin "A12_B1") (pinfunction "GND_A12_B1") (pintype "power_in"))
      (node (ref "J4") (pin "A1_B12") (pinfunction "GND_A1_B12") (pintype "power_in"))
      (node (ref "J4") (pin "SH1") (pinfunction "SHIELD_SH1") (pintype "passive"))
      (node (ref "J4") (pin "SH2") (pinfunction "SHIELD_SH2") (pintype "passive"))
      (node (ref "J4") (pin "SH3") (pinfunction "SHIELD_SH3") (pintype "passive"))
      (node (ref "J4") (pin "SH4") (pinfunction "SHIELD_SH4") (pintype "passive"))
      (node (ref "R1_USB") (pin "1") (pinfunction "1_1") (pintype "bidirectional"))
      (node (ref "R2_EP_DR") (pin "1") (pinfunction "1_1") (pintype "bidirectional"))
      (node (ref "R2_USB") (pin "2") (pinfunction "2_2") (pintype "bidirectional"))
      (node (ref "R3") (pin "1") (pinfunction "1_1") (pintype "bidirectional"))
      (node (ref "R9") (pin "1") (pinfunction "1_1") (pintype "bidirectional"))
      (node (ref "R_TYPE_SEL") (pin "1") (pinfunction "1_1") (pintype "bidirectional"))
      (node (ref "SJ1") (pin "1") (pinfunction "1_1") (pintype "passive"))
      (node (ref "SW_DN") (pin "1") (pinfunction "1_1") (pintype "passive"))
      (node (ref "SW_ENT") (pin "1") (pinfunction "1_1") (pintype "passive"))
      (node (ref "SW_UP") (pin "1") (pinfunction "1_1") (pintype "passive"))
      (node (ref "TP_BAT_GND") (pin "TP") (pinfunction "TP_TP") (pintype "input"))
      (node (ref "TP_GND") (pin "TP") (pinfunction "TP_TP") (pintype "input"))
      (node (ref "U1") (pin "P$74") (pinfunction "VSS_PAD_P$74") (pintype "bidirectional"))
      (node (ref "U1") (pin "P$75") (pinfunction "VSS_PAD_P$75") (pintype "bidirectional"))
      (node (ref "U1") (pin "P$76") (pinfunction "VSS_PAD_P$76") (pintype "bidirectional"))
      (node (ref "U1") (pin "P$77") (pinfunction "VSS_PAD_P$77") (pintype "bidirectional"))
      (node (ref "U1") (pin "P$78") (pinfunction "VSS_PAD_P$78") (pintype "bidirectional"))
      (node (ref "U1") (pin "P$79") (pinfunction "VSS_PAD_P$79") (pintype "bidirectional"))
      (node (ref "U1") (pin "P$80") (pinfunction "VSS_PAD_P$80") (pintype "bidirectional"))
      (node (ref "U1") (pin "P$81") (pinfunction "VSS_PAD_P$81") (pintype "bidirectional"))
      (node (ref "U1") (pin "P$82") (pinfunction "VSS_PAD_P$82") (pintype "bidirectional"))
      (node (ref "U1") (pin "P$83") (pinfunction "VSS_PAD_P$83") (pintype "bidirectional"))
      (node (ref "U1") (pin "P$84") (pinfunction "VSS_PAD_P$84") (pintype "bidirectional"))
      (node (ref "U1") (pin "P$85") (pinfunction "VSS_PAD_P$85") (pintype "bidirectional"))
      (node (ref "U1") (pin "P$86") (pinfunction "VSS_PAD_P$86") (pintype "bidirectional"))
      (node (ref "U1") (pin "P$87") (pinfunction "VSS_PAD_P$87") (pintype "bidirectional"))
      (node (ref "U1") (pin "P$88") (pinfunction "VSS_PAD_P$88") (pintype "bidirectional"))
      (node (ref "U1") (pin "P$89") (pinfunction "VSS_PAD_P$89") (pintype "bidirectional"))
      (node (ref "U1") (pin "P$90") (pinfunction "VSS_PAD_P$90") (pintype "bidirectional"))
      (node (ref "U1") (pin "P$B7") (pinfunction "VSS_P$B7") (pintype "power_in"))
      (node (ref "U1") (pin "P$F23") (pinfunction "VSS_PA_P$F23") (pintype "bidirectional"))
      (node (ref "U3") (pin "1") (pinfunction "CTG_1") (pintype "power_in"))
      (node (ref "U3") (pin "4") (pinfunction "GND_4") (pintype "power_in"))
      (node (ref "U3") (pin "6") (pinfunction "QSTRT_6") (pintype "input"))
      (node (ref "U3") (pin "9") (pinfunction "EP_9") (pintype "power_in"))
      (node (ref "X1") (pin "2") (pinfunction "2_2") (pintype "passive"))
      (node (ref "X1") (pin "4") (pinfunction "4_4") (pintype "passive"))
    )
    (net (code "15") (name "HAPTIC_EN") (class "Default")
      (node (ref "IC2") (pin "A1") (pinfunction "EN_A1") (pintype "bidirectional"))
      (node (ref "U1") (pin "P$U1") (pinfunction "P0.12_P$U1") (pintype "bidirectional"))
    )
    (net (code "16") (name "IMU_INT1") (class "Default")
      (node (ref "IC3") (pin "5") (pinfunction "INT1_5") (pintype "bidirectional"))
      (node (ref "U1") (pin "P$N1") (pinfunction "P0.08_P$N1") (pintype "bidirectional"))
    )
    (net (code "17") (name "IMU_INT2") (class "Default")
      (node (ref "IC3") (pin "6") (pinfunction "INT2_6") (pintype "bidirectional"))
      (node (ref "U1") (pin "P$P2") (pinfunction "P1.08_P$P2") (pintype "bidirectional"))
    )
    (net (code "18") (name "LX1") (class "Default")
      (node (ref "IC9") (pin "B2") (pinfunction "SW1_1_B2") (pintype "bidirectional"))
      (node (ref "IC9") (pin "B3") (pinfunction "SW1_2_B3") (pintype "bidirectional"))
      (node (ref "L7") (pin "1") (pinfunction "1_1") (pintype "bidirectional"))
    )
    (net (code "19") (name "LX2") (class "Default")
      (node (ref "IC9") (pin "D2") (pinfunction "SW2_1_D2") (pintype "bidirectional"))
      (node (ref "IC9") (pin "D3") (pinfunction "SW2_2_D3") (pintype "bidirectional"))
      (node (ref "L7") (pin "2") (pinfunction "2_2") (pintype "bidirectional"))
    )
    (net (code "20") (name "MOSI") (class "Default")
      (node (ref "J1") (pin "14") (pinfunction "14_14") (pintype "bidirectional"))
      (node (ref "U1") (pin "P$B13") (pinfunction "P0.03/AIN1_P$B13") (pintype "bidirectional"))
    )
    (net (code "21") (name "Net-(ANT1-FEED)") (class "Default")
      (node (ref "ANT1") (pin "1") (pinfunction "FEED_1") (pintype "input"))
      (node (ref "C22") (pin "1") (pinfunction "1_1") (pintype "passive"))
      (node (ref "C4") (pin "1") (pinfunction "1_1") (pintype "passive"))
      (node (ref "L1") (pin "2") (pinfunction "2_2") (pintype "passive"))
    )
    (net (code "22") (name "Net-(D2-K)") (class "Default")
      (node (ref "C2-EP-DR") (pin "1") (pinfunction "1_1") (pintype "passive"))
      (node (ref "D2") (pin "1") (pinfunction "K_1") (pintype "bidirectional"))
      (node (ref "D4") (pin "2") (pinfunction "A_2") (pintype "bidirectional"))
    )
    (net (code "23") (name "Net-(D5-A)") (class "Default")
      (node (ref "C2-EP-DR") (pin "2") (pinfunction "2_2") (pintype "passive"))
      (node (ref "D5") (pin "2") (pinfunction "A_2") (pintype "bidirectional"))
      (node (ref "L5") (pin "2") (pinfunction "2_2") (pintype "passive"))
      (node (ref "Q3") (pin "3") (pinfunction "D_3") (pintype "bidirectional"))
    )
    (net (code "24") (name "Net-(EPD_C1-Pad2)") (class "Default")
      (node (ref "EPD_C1") (pin "2") (pinfunction "2_2") (pintype "passive"))
      (node (ref "J1") (pin "5") (pinfunction "5_5") (pintype "bidirectional"))
    )
    (net (code "25") (name "Net-(EPD_C2-Pad2)") (class "Default")
      (node (ref "EPD_C2") (pin "2") (pinfunction "2_2") (pintype "passive"))
      (node (ref "J1") (pin "4") (pinfunction "4_4") (pintype "bidirectional"))
    )
    (net (code "26") (name "Net-(EPD_C6-Pad2)") (class "Default")
      (node (ref "EPD_C6") (pin "2") (pinfunction "2_2") (pintype "passive"))
      (node (ref "J1") (pin "18") (pinfunction "18_18") (pintype "bidirectional"))
    )
    (net (code "27") (name "Net-(EPD_C7-Pad2)") (class "Default")
      (node (ref "EPD_C7") (pin "2") (pinfunction "2_2") (pintype "passive"))
      (node (ref "J1") (pin "19") (pinfunction "19_19") (pintype "bidirectional"))
    )
    (net (code "28") (name "Net-(EPD_C8-Pad2)") (class "Default")
      (node (ref "EPD_C8") (pin "2") (pinfunction "2_2") (pintype "passive"))
      (node (ref "J1") (pin "20") (pinfunction "20_20") (pintype "bidirectional"))
    )
    (net (code "29") (name "Net-(EPD_C10-Pad2)") (class "Default")
      (node (ref "EPD_C10") (pin "2") (pinfunction "2_2") (pintype "passive"))
      (node (ref "J1") (pin "22") (pinfunction "22_22") (pintype "bidirectional"))
    )
    (net (code "30") (name "Net-(EPD_C12-Pad2)") (class "Default")
      (node (ref "EPD_C12") (pin "2") (pinfunction "2_2") (pintype "passive"))
      (node (ref "J1") (pin "24") (pinfunction "24_24") (pintype "bidirectional"))
    )
    (net (code "31") (name "Net-(IC1-TS{slash}MR)") (class "Default")
      (node (ref "IC1") (pin "D1") (pinfunction "TS/MR_D1") (pintype "bidirectional"))
      (node (ref "R9") (pin "2") (pinfunction "2_2") (pintype "bidirectional"))
    )
    (net (code "32") (name "Net-(IC2-REG)") (class "Default")
      (node (ref "C32") (pin "2") (pinfunction "2_2") (pintype "passive"))
      (node (ref "IC2") (pin "A2") (pinfunction "REG_A2") (pintype "bidirectional"))
    )
    (net (code "33") (name "Net-(IC3-SDO)") (class "Default")
      (node (ref "IC3") (pin "1") (pinfunction "SDO_1") (pintype "bidirectional"))
      (node (ref "R3") (pin "2") (pinfunction "2_2") (pintype "bidirectional"))
    )
    (net (code "34") (name "Net-(IC9-SCL)") (class "Default")
      (node (ref "IC9") (pin "D1") (pinfunction "SCL_D1") (pintype "bidirectional"))
      (node (ref "R4") (pin "2") (pinfunction "2_2") (pintype "bidirectional"))
    )
    (net (code "35") (name "Net-(IC9-SDA)") (class "Default")
      (node (ref "IC9") (pin "E1") (pinfunction "SDA_E1") (pintype "bidirectional"))
      (node (ref "R2") (pin "2") (pinfunction "2_2") (pintype "bidirectional"))
    )
    (net (code "36") (name "Net-(J4-CC1)") (class "Default")
      (node (ref "J4") (pin "A5") (pinfunction "CC1_A5") (pintype "bidirectional"))
      (node (ref "R1_USB") (pin "2") (pinfunction "2_2") (pintype "bidirectional"))
    )
    (net (code "37") (name "Net-(J4-CC2)") (class "Default")
      (node (ref "J4") (pin "B5") (pinfunction "CC2_B5") (pintype "bidirectional"))
      (node (ref "R2_USB") (pin "1") (pinfunction "1_1") (pintype "bidirectional"))
    )
    (net (code "38") (name "Net-(L2-Pad1)") (class "Default")
      (node (ref "L2") (pin "1") (pinfunction "1_1") (pintype "passive"))
      (node (ref "L3") (pin "2") (pinfunction "2_2") (pintype "passive"))
    )
    (net (code "39") (name "Net-(R1_EP_DR-Pad1)") (class "Default")
      (node (ref "R1_EP_DR") (pin "1") (pinfunction "1_1") (pintype "bidirectional"))
      (node (ref "R_TYPE_SEL") (pin "2") (pinfunction "2_2") (pintype "bidirectional"))
      (node (ref "SJ1") (pin "2") (pinfunction "2_2") (pintype "passive"))
    )
    (net (code "40") (name "Net-(U1-ANT)") (class "Default")
      (node (ref "C3") (pin "1") (pinfunction "1_1") (pintype "passive"))
      (node (ref "L1") (pin "1") (pinfunction "1_1") (pintype "passive"))
      (node (ref "U1") (pin "P$H23") (pinfunction "ANT_P$H23") (pintype "bidirectional"))
    )
    (net (code "41") (name "Net-(U1-DCC)") (class "Default")
      (node (ref "L2") (pin "2") (pinfunction "2_2") (pintype "passive"))
      (node (ref "U1") (pin "P$B3") (pinfunction "DCC_P$B3") (pintype "output"))
    )
    (net (code "42") (name "Net-(U1-DEC1)") (class "Default")
      (node (ref "C5") (pin "2") (pinfunction "2_2") (pintype "passive"))
      (node (ref "U1") (pin "P$C1") (pinfunction "DEC1_P$C1") (pintype "power_in"))
    )
    (net (code "43") (name "Net-(U1-DEC2)") (class "Default")
      (node (ref "C13") (pin "1") (pinfunction "1_1") (pintype "passive"))
      (node (ref "U1") (pin "P$A18") (pinfunction "DEC2_P$A18") (pintype "bidirectional"))
    )
    (net (code "44") (name "Net-(U1-DEC3)") (class "Default")
      (node (ref "C11") (pin "1") (pinfunction "1_1") (pintype "passive"))
      (node (ref "U1") (pin "P$D23") (pinfunction "DEC3_P$D23") (pintype "bidirectional"))
    )
    (net (code "45") (name "Net-(U1-DEC3V3)") (class "Default")
      (node (ref "C20") (pin "1") (pinfunction "1_1") (pintype "passive"))
      (node (ref "U1") (pin "P$AC5") (pinfunction "DEC3V3_P$AC5") (pintype "bidirectional"))
    )
    (net (code "46") (name "Net-(U1-DEC4)") (class "Default")
      (node (ref "C10") (pin "1") (pinfunction "1_1") (pintype "passive"))
      (node (ref "C15") (pin "1") (pinfunction "1_1") (pintype "passive"))
      (node (ref "C16") (pin "1") (pinfunction "1_1") (pintype "passive"))
      (node (ref "L3") (pin "1") (pinfunction "1_1") (pintype "passive"))
      (node (ref "U1") (pin "P$B5") (pinfunction "DEC4_P$B5") (pintype "power_in"))
      (node (ref "U1") (pin "P$E24") (pinfunction "DEC6_P$E24") (pintype "bidirectional"))
    )
    (net (code "47") (name "Net-(U1-DEC5)") (class "Default")
      (node (ref "C9") (pin "1") (pinfunction "1_1") (pintype "passive"))
      (node (ref "U1") (pin "P$N24") (pinfunction "DEC5_P$N24") (pintype "bidirectional"))
    )
    (net (code "48") (name "Net-(U1-P0.00{slash}XL1)") (class "Default")
      (node (ref "C17") (pin "2") (pinfunction "2_2") (pintype "passive"))
      (node (ref "U1") (pin "P$D2") (pinfunction "P0.00/XL1_P$D2") (pintype "bidirectional"))
      (node (ref "X2") (pin "1") (pinfunction "1_1") (pintype "passive"))
    )
    (net (code "49") (name "Net-(U1-P0.01{slash}XL2)") (class "Default")
      (node (ref "C18") (pin "2") (pinfunction "2_2") (pintype "passive"))
      (node (ref "U1") (pin "P$F2") (pinfunction "P0.01/XL2_P$F2") (pintype "bidirectional"))
      (node (ref "X2") (pin "2") (pinfunction "2_2") (pintype "passive"))
    )
    (net (code "50") (name "Net-(U1-XC1)") (class "Default")
      (node (ref "C1") (pin "1") (pinfunction "1_1") (pintype "passive"))
      (node (ref "U1") (pin "P$B24") (pinfunction "XC1_P$B24") (pintype "input"))
      (node (ref "X1") (pin "1") (pinfunction "1_1") (pintype "passive"))
    )
    (net (code "51") (name "Net-(U1-XC2)") (class "Default")
      (node (ref "C2") (pin "1") (pinfunction "1_1") (pintype "passive"))
      (node (ref "U1") (pin "P$A23") (pinfunction "XC2_P$A23") (pintype "output"))
      (node (ref "X1") (pin "3") (pinfunction "3_3") (pintype "passive"))
    )
    (net (code "52") (name "OUT+") (class "Default")
      (node (ref "IC2") (pin "A3") (pinfunction "OUT+_A3") (pintype "bidirectional"))
      (node (ref "TP_OP") (pin "TP") (pinfunction "TP_TP") (pintype "input"))
    )
    (net (code "53") (name "OUT-") (class "Default")
      (node (ref "IC2") (pin "C3") (pinfunction "OUT-_C3") (pintype "bidirectional"))
      (node (ref "TP_ON") (pin "TP") (pinfunction "TP_TP") (pintype "input"))
    )
    (net (code "54") (name "P0.04") (class "Default")
      (node (ref "U1") (pin "P$J1") (pinfunction "P0.04/AIN2_P$J1") (pintype "bidirectional"))
    )
    (net (code "55") (name "P0.09") (class "Default")
      (node (ref "U1") (pin "P$L24") (pinfunction "P0.09/NFC1_P$L24") (pintype "bidirectional"))
    )
    (net (code "56") (name "P0.13") (class "Default")
      (node (ref "U1") (pin "P$AD8") (pinfunction "P0.13_P$AD8") (pintype "bidirectional"))
    )
    (net (code "57") (name "P0.13{slash}1.5D") (class "Default")
      (node (ref "C30") (pin "2") (pinfunction "2_2") (pintype "passive"))
      (node (ref "R5") (pin "1") (pinfunction "1_1") (pintype "bidirectional"))
      (node (ref "SW_UP") (pin "2") (pinfunction "2_2") (pintype "passive"))
    )
    (net (code "58") (name "P0.14") (class "Default")
      (node (ref "U1") (pin "P$AC9") (pinfunction "P0.14_P$AC9") (pintype "bidirectional"))
    )
    (net (code "59") (name "P0.14{slash}1.5D") (class "Default")
      (node (ref "C31") (pin "2") (pinfunction "2_2") (pintype "passive"))
      (node (ref "R8") (pin "1") (pinfunction "1_1") (pintype "bidirectional"))
      (node (ref "SW_ENT") (pin "2") (pinfunction "2_2") (pintype "passive"))
    )
    (net (code "60") (name "P0.19") (class "Default")
      (node (ref "U1") (pin "P$AC15") (pinfunction "P0.19_P$AC15") (pintype "bidirectional"))
    )
    (net (code "61") (name "P0.20") (class "Default")
      (node (ref "U1") (pin "P$AD16") (pinfunction "P0.20_P$AD16") (pintype "bidirectional"))
    )
    (net (code "62") (name "P0.21") (class "Default")
      (node (ref "U1") (pin "P$AC17") (pinfunction "P0.21_P$AC17") (pintype "bidirectional"))
    )
    (net (code "63") (name "P0.22") (class "Default")
      (node (ref "U1") (pin "P$AD18") (pinfunction "P0.22_P$AD18") (pintype "bidirectional"))
    )
    (net (code "64") (name "P0.23") (class "Default")
      (node (ref "U1") (pin "P$AC19") (pinfunction "P0.23_P$AC19") (pintype "bidirectional"))
    )
    (net (code "65") (name "P0.24") (class "Default")
      (node (ref "U1") (pin "P$AD20") (pinfunction "P0.24_P$AD20") (pintype "bidirectional"))
    )
    (net (code "66") (name "P0.25") (class "Default")
      (node (ref "U1") (pin "P$AC21") (pinfunction "P0.25_P$AC21") (pintype "bidirectional"))
    )
    (net (code "67") (name "P0.26") (class "Default")
      (node (ref "U1") (pin "P$G1") (pinfunction "P0.26_P$G1") (pintype "bidirectional"))
    )
    (net (code "68") (name "P0.27") (class "Default")
      (node (ref "U1") (pin "P$H2") (pinfunction "P0.27_P$H2") (pintype "bidirectional"))
    )
    (net (code "69") (name "P1.01") (class "Default")
      (node (ref "U1") (pin "P$Y23") (pinfunction "P1.01_P$Y23") (pintype "bidirectional"))
    )
    (net (code "70") (name "P1.01{slash}1.6C") (class "Default")
      (node (ref "Q1") (pin "1") (pinfunction "G_1") (pintype "bidirectional"))
      (node (ref "R_PWR_EPD") (pin "1") (pinfunction "1_1") (pintype "bidirectional"))
    )
    (net (code "71") (name "P1.02") (class "Default")
      (node (ref "U1") (pin "P$W24") (pinfunction "P1.02_P$W24") (pintype "bidirectional"))
    )
    (net (code "72") (name "P1.02{slash}1.6C") (class "Default")
      (node (ref "C29") (pin "2") (pinfunction "2_2") (pintype "passive"))
      (node (ref "R7") (pin "1") (pinfunction "1_1") (pintype "bidirectional"))
      (node (ref "SW_DN") (pin "2") (pinfunction "2_2") (pintype "passive"))
    )
    (net (code "73") (name "P1.03") (class "Default")
      (node (ref "U1") (pin "P$V23") (pinfunction "P1.03_P$V23") (pintype "bidirectional"))
    )
    (net (code "74") (name "P1.04") (class "Default")
      (node (ref "U1") (pin "P$U24") (pinfunction "P1.04_P$U24") (pintype "bidirectional"))
    )
    (net (code "75") (name "P1.05") (class "Default")
      (node (ref "U1") (pin "P$T23") (pinfunction "P1.05_P$T23") (pintype "bidirectional"))
    )
    (net (code "76") (name "P1.06") (class "Default")
      (node (ref "U1") (pin "P$R24") (pinfunction "P1.06_P$R24") (pintype "bidirectional"))
    )
    (net (code "77") (name "P1.07") (class "Default")
      (node (ref "U1") (pin "P$P23") (pinfunction "P1.07_P$P23") (pintype "bidirectional"))
    )
    (net (code "78") (name "P1.09") (class "Default")
      (node (ref "U1") (pin "P$R1") (pinfunction "P1.09_P$R1") (pintype "bidirectional"))
    )
    (net (code "79") (name "P1.10") (class "Default")
      (node (ref "U1") (pin "P$A20") (pinfunction "P1.10_P$A20") (pintype "bidirectional"))
    )
    (net (code "80") (name "P1.11") (class "Default")
      (node (ref "U1") (pin "P$B19") (pinfunction "P1.11_P$B19") (pintype "bidirectional"))
    )
    (net (code "81") (name "P1.12") (class "Default")
      (node (ref "U1") (pin "P$B17") (pinfunction "P1.12_P$B17") (pintype "bidirectional"))
    )
    (net (code "82") (name "P1.13") (class "Default")
      (node (ref "U1") (pin "P$A16") (pinfunction "P1.13_P$A16") (pintype "bidirectional"))
    )
    (net (code "83") (name "P1.14") (class "Default")
      (node (ref "U1") (pin "P$B15") (pinfunction "P1.14_P$B15") (pintype "bidirectional"))
    )
    (net (code "84") (name "P1.15") (class "Default")
      (node (ref "U1") (pin "P$A14") (pinfunction "P1.15_P$A14") (pintype "bidirectional"))
    )
    (net (code "85") (name "P1.28") (class "Default")
      (node (ref "U1") (pin "P$B11") (pinfunction "P0.28/AIN4_P$B11") (pintype "bidirectional"))
    )
    (net (code "86") (name "P1.29") (class "Default")
      (node (ref "U1") (pin "P$A10") (pinfunction "P0.29/AIN5_P$A10") (pintype "bidirectional"))
    )
    (net (code "87") (name "P1.30") (class "Default")
      (node (ref "U1") (pin "P$B9") (pinfunction "P0.30/AIN6_P$B9") (pintype "bidirectional"))
    )
    (net (code "88") (name "P1.31") (class "Default")
      (node (ref "U1") (pin "P$A8") (pinfunction "P0.31/AIN7_P$A8") (pintype "bidirectional"))
    )
    (net (code "89") (name "PMIC_INT") (class "Default")
      (node (ref "IC1") (pin "A1") (pinfunction "~{INT}_A1") (pintype "bidirectional"))
      (node (ref "U1") (pin "P$T2") (pinfunction "P0.11_P$T2") (pintype "bidirectional"))
    )
    (net (code "90") (name "PREVGH") (class "Default")
      (node (ref "D5") (pin "1") (pinfunction "K_1") (pintype "bidirectional"))
      (node (ref "EPD_C9") (pin "2") (pinfunction "2_2") (pintype "passive"))
      (node (ref "J1") (pin "21") (pinfunction "21_21") (pintype "bidirectional"))
    )
    (net (code "91") (name "PREVGL") (class "Default")
      (node (ref "D2") (pin "2") (pinfunction "A_2") (pintype "bidirectional"))
      (node (ref "EPD_C11") (pin "2") (pinfunction "2_2") (pintype "passive"))
      (node (ref "J1") (pin "23") (pinfunction "23_23") (pintype "bidirectional"))
    )
    (net (code "92") (name "RESE") (class "Default")
      (node (ref "J1") (pin "3") (pinfunction "3_3") (pintype "bidirectional"))
      (node (ref "Q3") (pin "2") (pinfunction "S_2") (pintype "bidirectional"))
      (node (ref "R1_EP_DR") (pin "2") (pinfunction "2_2") (pintype "bidirectional"))
    )
    (net (code "93") (name "RESET") (class "Default")
      (node (ref "J2") (pin "6") (pinfunction "6_6") (pintype "bidirectional"))
      (node (ref "TP_RESET") (pin "TP") (pinfunction "TP_TP") (pintype "input"))
      (node (ref "U1") (pin "P$AC13") (pinfunction "P0.18/RESET_P$AC13") (pintype "bidirectional"))
    )
    (net (code "94") (name "SCK") (class "Default")
      (node (ref "J1") (pin "13") (pinfunction "13_13") (pintype "bidirectional"))
      (node (ref "U1") (pin "P$A12") (pinfunction "P0.02/AIN0_P$A12") (pintype "bidirectional"))
    )
    (net (code "95") (name "SCL{slash}1.4C") (class "Default")
      (node (ref "IC2") (pin "C1") (pinfunction "SCL_C1") (pintype "bidirectional"))
      (node (ref "U3") (pin "7") (pinfunction "SCL_7") (pintype "input"))
    )
    (net (code "96") (name "SCL{slash}2.4C") (class "Default")
      (node (ref "IC1") (pin "B1") (pinfunction "SCL_B1") (pintype "bidirectional"))
      (node (ref "IC3") (pin "12") (pinfunction "SCX_12") (pintype "bidirectional"))
      (node (ref "R17") (pin "2") (pinfunction "2_2") (pintype "bidirectional"))
      (node (ref "R18") (pin "2") (pinfunction "2_2") (pintype "bidirectional"))
      (node (ref "R4") (pin "1") (pinfunction "1_1") (pintype "bidirectional"))
      (node (ref "TP_SCL") (pin "TP") (pinfunction "TP_TP") (pintype "input"))
      (node (ref "TP_SDA") (pin "TP") (pinfunction "TP_TP") (pintype "input"))
      (node (ref "U1") (pin "P$M2") (pinfunction "P0.07_P$M2") (pintype "bidirectional"))
    )
    (net (code "97") (name "SDA{slash}1.4C") (class "Default")
      (node (ref "IC2") (pin "B2") (pinfunction "SDA_B2") (pintype "bidirectional"))
      (node (ref "U3") (pin "8") (pinfunction "SDA_8") (pintype "bidirectional"))
    )
    (net (code "98") (name "SDA{slash}2.4C") (class "Default")
      (node (ref "IC1") (pin "C1") (pinfunction "SDA_C1") (pintype "bidirectional"))
      (node (ref "IC3") (pin "2") (pinfunction "SDX_2") (pintype "bidirectional"))
      (node (ref "R2") (pin "1") (pinfunction "1_1") (pintype "bidirectional"))
      (node (ref "U1") (pin "P$L1") (pinfunction "P0.06_P$L1") (pintype "bidirectional"))
    )
    (net (code "99") (name "SWDCLK") (class "Default")
      (node (ref "J2") (pin "4") (pinfunction "4_4") (pintype "bidirectional"))
      (node (ref "TP_SWDCLK") (pin "TP") (pinfunction "TP_TP") (pintype "input"))
      (node (ref "U1") (pin "P$AA24") (pinfunction "SWDCLK_P$AA24") (pintype "input"))
    )
    (net (code "100") (name "SWDIO") (class "Default")
      (node (ref "J2") (pin "2") (pinfunction "2_2") (pintype "bidirectional"))
      (node (ref "TP_SWDIO") (pin "TP") (pinfunction "TP_TP") (pintype "input"))
      (node (ref "U1") (pin "P$AC24") (pinfunction "SWDIO_P$AC24") (pintype "bidirectional"))
    )
    (net (code "101") (name "SWO") (class "Default")
      (node (ref "TP_SWO") (pin "TP") (pinfunction "TP_TP") (pintype "input"))
      (node (ref "U1") (pin "P$AD22") (pinfunction "P1.00_P$AD22") (pintype "bidirectional"))
    )
    (net (code "102") (name "VBAT{slash}1.2A") (class "Default")
      (node (ref "C27") (pin "2") (pinfunction "2_2") (pintype "passive"))
      (node (ref "TP_VBAT") (pin "TP") (pinfunction "TP_TP") (pintype "input"))
      (node (ref "U3") (pin "2") (pinfunction "CELL_2") (pintype "power_in"))
      (node (ref "U3") (pin "3") (pinfunction "VDD_3") (pintype "power_in"))
    )
    (net (code "103") (name "VBAT{slash}2.5C") (class "Default")
      (node (ref "C37") (pin "2") (pinfunction "2_2") (pintype "passive"))
      (node (ref "IC1") (pin "C2") (pinfunction "BAT_C2") (pintype "bidirectional"))
    )
    (net (code "104") (name "VBUS{slash}1.5D") (class "Default")
      (node (ref "C42") (pin "1") (pinfunction "1_1") (pintype "passive"))
      (node (ref "C43") (pin "1") (pinfunction "1_1") (pintype "passive"))
      (node (ref "D3") (pin "5") (pinfunction "VBUS_5") (pintype "bidirectional"))
      (node (ref "J4") (pin "A4_B9") (pinfunction "VBUS_A4_B9") (pintype "power_in"))
      (node (ref "J4") (pin "A9_B4") (pinfunction "VBUS_A9_B4") (pintype "power_in"))
    )
    (net (code "105") (name "VBUS{slash}2.6D") (class "Default")
      (node (ref "C21") (pin "1") (pinfunction "1_1") (pintype "passive"))
      (node (ref "C38") (pin "2") (pinfunction "2_2") (pintype "passive"))
      (node (ref "IC1") (pin "A2") (pinfunction "IN_A2") (pintype "bidirectional"))
      (node (ref "U1") (pin "P$AD2") (pinfunction "VBUS_P$AD2") (pintype "power_in"))
    )
    (net (code "106") (name "VREG") (class "Default")
      (node (ref "C23") (pin "2") (pinfunction "2_2") (pintype "passive"))
      (node (ref "C24") (pin "2") (pinfunction "2_2") (pintype "passive"))
      (node (ref "C39") (pin "1") (pinfunction "1_1") (pintype "passive"))
      (node (ref "IC1") (pin "B2") (pinfunction "SYS_B2") (pintype "bidirectional"))
      (node (ref "IC9") (pin "A1") (pinfunction "EN_A1") (pintype "bidirectional"))
      (node (ref "IC9") (pin "A2") (pinfunction "VIN_1_A2") (pintype "bidirectional"))
      (node (ref "IC9") (pin "A3") (pinfunction "VIN_2_A3") (pintype "bidirectional"))
      (node (ref "TP_VREG") (pin "TP") (pinfunction "TP_TP") (pintype "input"))
    )
    (net (code "107") (name "unconnected-(ANT1-NC-Pad2)") (class "Default")
      (node (ref "ANT1") (pin "2") (pinfunction "NC_2") (pintype "no_connect"))
    )
    (net (code "108") (name "unconnected-(IC3-ASCL-Pad11)") (class "Default")
      (node (ref "IC3") (pin "11") (pinfunction "ASCL_11") (pintype "bidirectional"))
    )
    (net (code "109") (name "unconnected-(IC3-ASDA-Pad4)") (class "Default")
      (node (ref "IC3") (pin "4") (pinfunction "ASDA_4") (pintype "bidirectional"))
    )
    (net (code "110") (name "unconnected-(J1-Pad1)") (class "Default")
      (node (ref "J1") (pin "1") (pinfunction "1_1") (pintype "bidirectional"))
    )
    (net (code "111") (name "unconnected-(J1-Pad6)") (class "Default")
      (node (ref "J1") (pin "6") (pinfunction "6_6") (pintype "bidirectional"))
    )
    (net (code "112") (name "unconnected-(J1-Pad7)") (class "Default")
      (node (ref "J1") (pin "7") (pinfunction "7_7") (pintype "bidirectional"))
    )
    (net (code "113") (name "unconnected-(J4-SBU1-PadA8)") (class "Default")
      (node (ref "J4") (pin "A8") (pinfunction "SBU1_A8") (pintype "bidirectional"))
    )
    (net (code "114") (name "unconnected-(J4-SBU2-PadB8)") (class "Default")
      (node (ref "J4") (pin "B8") (pinfunction "SBU2_B8") (pintype "bidirectional"))
    )
    (net (code "115") (name "unconnected-(U1-DCCH-PadP$AB2)") (class "Default")
      (node (ref "U1") (pin "P$AB2") (pinfunction "DCCH_P$AB2") (pintype "bidirectional"))
    )
  )
)
